# MC50_CPU.net
KiCad netlist of a schematic drawn in Altium Designer
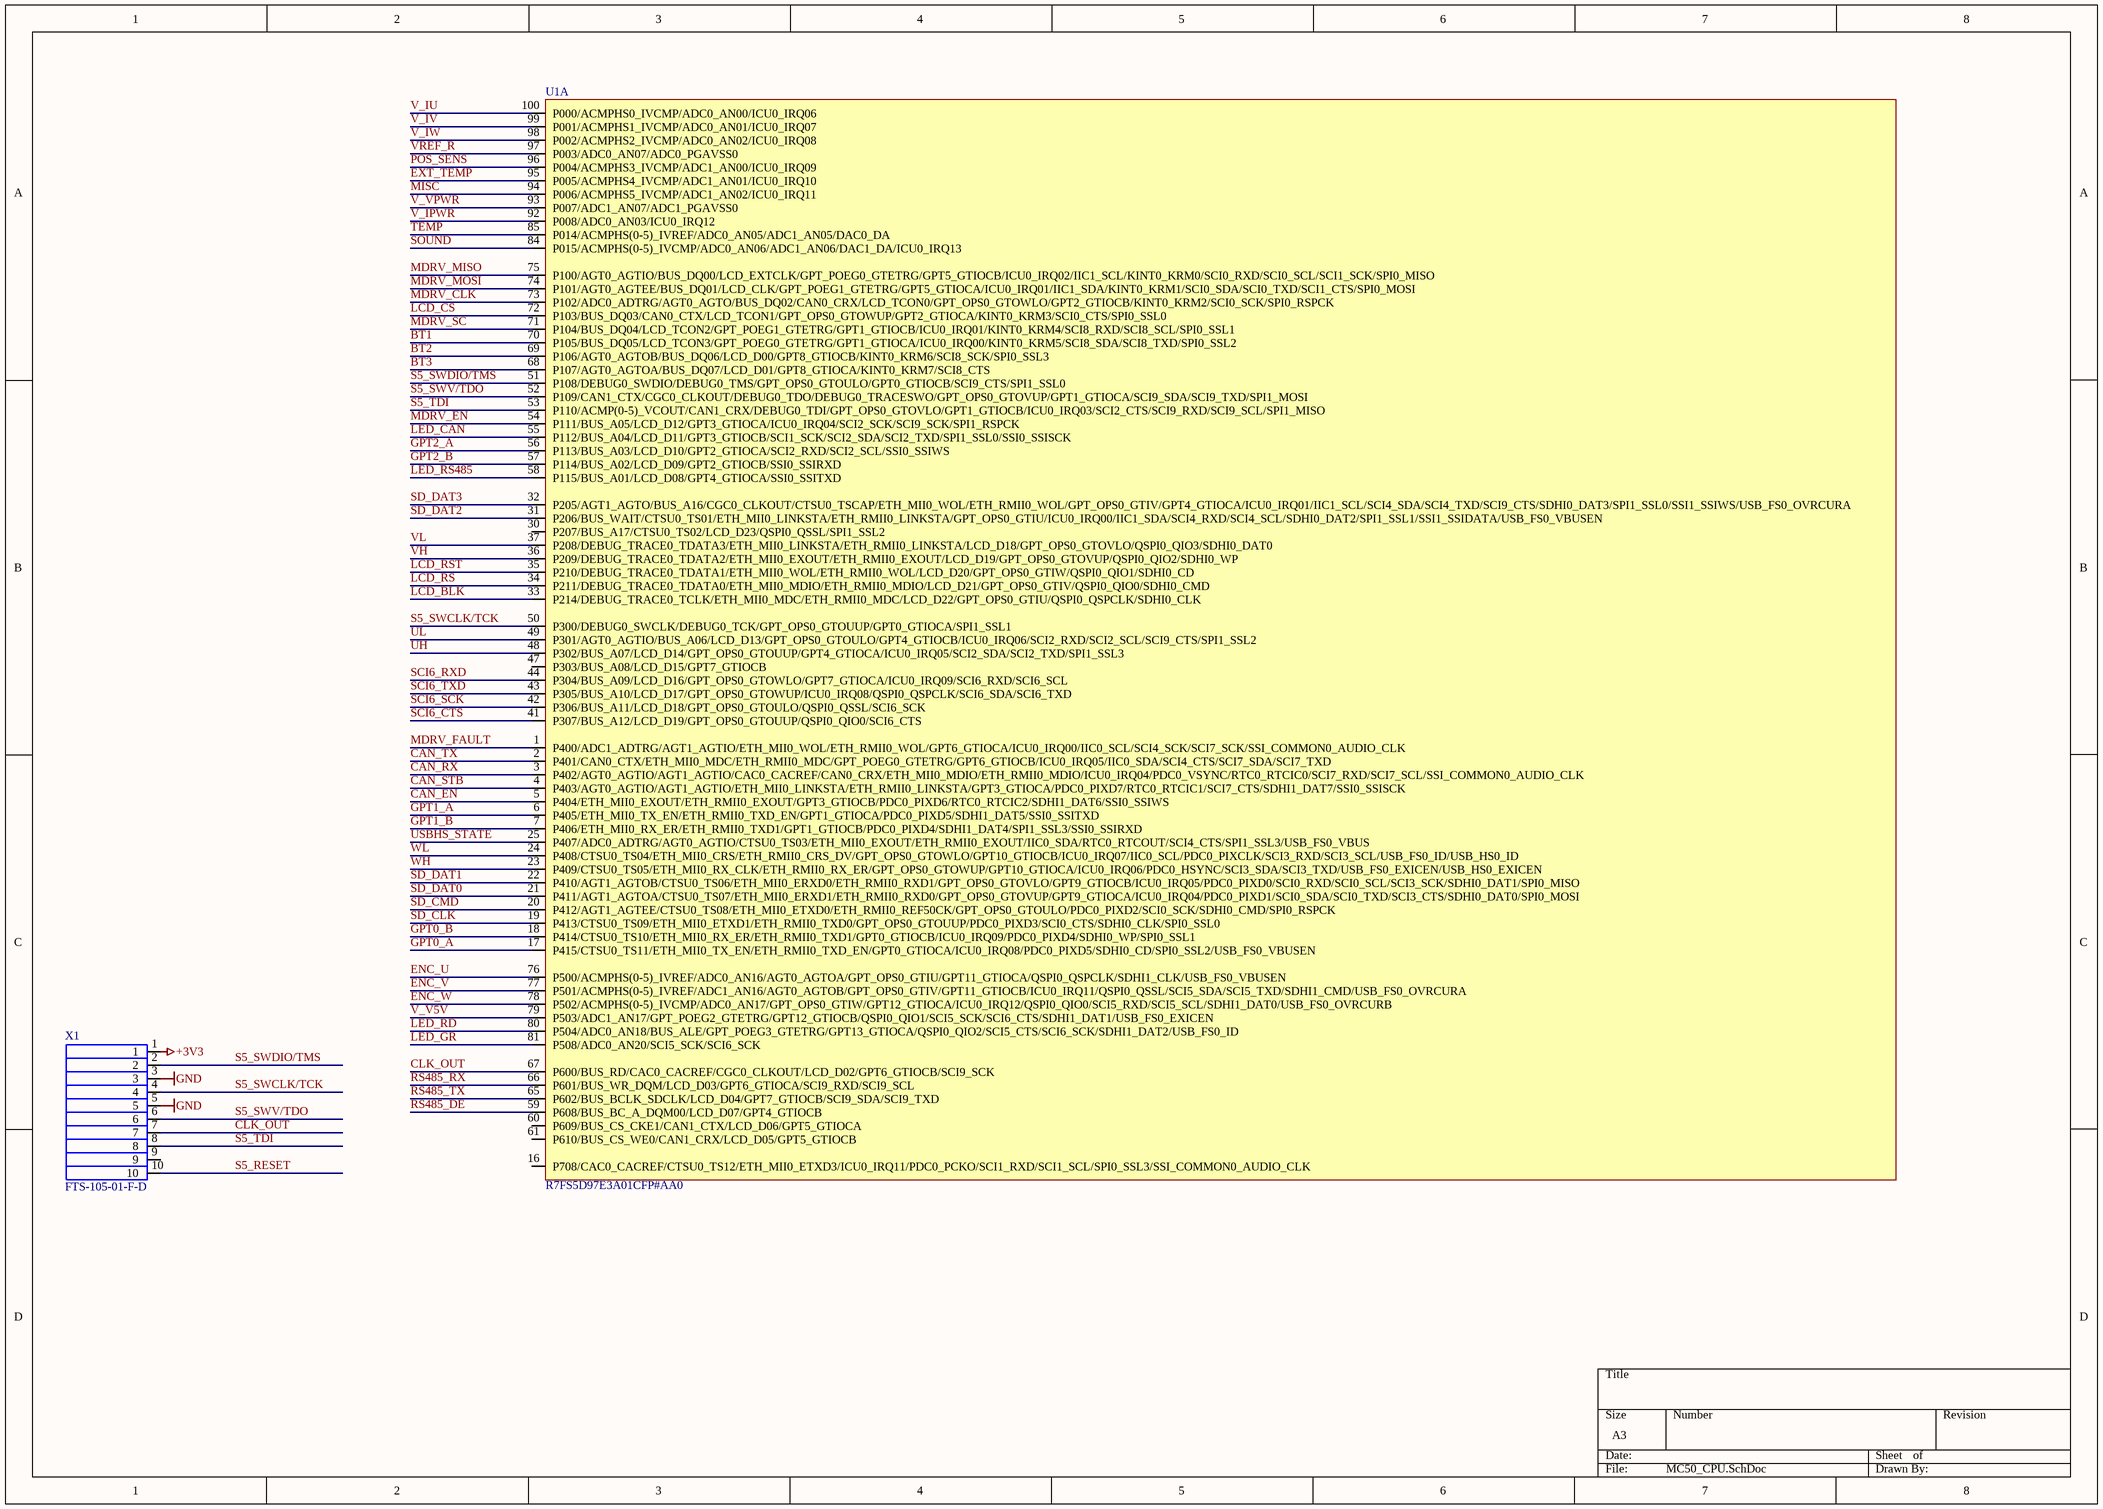
[diagram p0: MC50_CPU.SchDoc]

(export (version "E")
  (design (tool "Eeschema 10.0.6"))
  (components
    (comp (ref "U1")
      (value "R7FS5D97E3A01CFP#AA0")
      (footprint "P-LFQFP100-14x14-0.50")
      (fields (field (name "MANUFACTURER") "Renesas") (field (name "PARTNUM") "968-S5D97E3A01CFPAA0"))
      (libsource (lib "ea_IC_CPU") (part "R7FS5D97E3A01CFP#AA0"))
    )
    (comp (ref "X1")
      (value "FTS-105-01-F-D")
      (footprint "FTS-105-01-F-D")
      (description "Board-To-Board Connector, Vertical, FTS Series, Through Hole, Header, 10, 1.27 mm")
      (fields (field (name "MANUFACTURER") "SAMTEC") (field (name "PARTNUM") "1928242"))
      (libsource (lib "ea_JTAG_SWD") (part "FTS-105-01-F-D"))
    )
  )
  (nets
    (net (code "1") (name "+3V3") (class "Default")
      (node (ref "X1") (pin "1") (pinfunction "1_1") (pintype "passive"))
    )
    (net (code "2") (name "/BT1") (class "Default")
      (node (ref "U1") (pin "70") (pinfunction "P105/BUS_DQ05/LCD_TCON3/GPT_POEG0_GTETRG/GPT1_GTIOCA/ICU0_IRQ00/KINT0_KRM5/SCI8_SDA/SCI8_TXD/SPI0_SSL2_70") (pintype "bidirectional"))
    )
    (net (code "3") (name "/BT2") (class "Default")
      (node (ref "U1") (pin "69") (pinfunction "P106/AGT0_AGTOB/BUS_DQ06/LCD_D00/GPT8_GTIOCB/KINT0_KRM6/SCI8_SCK/SPI0_SSL3_69") (pintype "bidirectional"))
    )
    (net (code "4") (name "/BT3") (class "Default")
      (node (ref "U1") (pin "68") (pinfunction "P107/AGT0_AGTOA/BUS_DQ07/LCD_D01/GPT8_GTIOCA/KINT0_KRM7/SCI8_CTS_68") (pintype "bidirectional"))
    )
    (net (code "5") (name "/CAN_EN") (class "Default")
      (node (ref "U1") (pin "5") (pinfunction "P404/ETH_MII0_EXOUT/ETH_RMII0_EXOUT/GPT3_GTIOCB/PDC0_PIXD6/RTC0_RTCIC2/SDHI1_DAT6/SSI0_SSIWS_5") (pintype "bidirectional"))
    )
    (net (code "6") (name "/CAN_RX") (class "Default")
      (node (ref "U1") (pin "3") (pinfunction "P402/AGT0_AGTIO/AGT1_AGTIO/CAC0_CACREF/CAN0_CRX/ETH_MII0_MDIO/ETH_RMII0_MDIO/ICU0_IRQ04/PDC0_VSYNC/RTC0_RTCIC0/SCI7_RXD/SCI7_SCL/SSI_COMMON0_AUDIO_CLK_3") (pintype "bidirectional"))
    )
    (net (code "7") (name "/CAN_STB") (class "Default")
      (node (ref "U1") (pin "4") (pinfunction "P403/AGT0_AGTIO/AGT1_AGTIO/ETH_MII0_LINKSTA/ETH_RMII0_LINKSTA/GPT3_GTIOCA/PDC0_PIXD7/RTC0_RTCIC1/SCI7_CTS/SDHI1_DAT7/SSI0_SSISCK_4") (pintype "bidirectional"))
    )
    (net (code "8") (name "/CAN_TX") (class "Default")
      (node (ref "U1") (pin "2") (pinfunction "P401/CAN0_CTX/ETH_MII0_MDC/ETH_RMII0_MDC/GPT_POEG0_GTETRG/GPT6_GTIOCB/ICU0_IRQ05/IIC0_SDA/SCI4_CTS/SCI7_SDA/SCI7_TXD_2") (pintype "bidirectional"))
    )
    (net (code "9") (name "/CLK_OUT") (class "Default")
      (node (ref "U1") (pin "67") (pinfunction "P600/BUS_RD/CAC0_CACREF/CGC0_CLKOUT/LCD_D02/GPT6_GTIOCB/SCI9_SCK_67") (pintype "bidirectional"))
      (node (ref "X1") (pin "7") (pinfunction "7_7") (pintype "power_in"))
    )
    (net (code "10") (name "/ENC_U") (class "Default")
      (node (ref "U1") (pin "76") (pinfunction "P500/ACMPHS(0-5)_IVREF/ADC0_AN16/AGT0_AGTOA/GPT_OPS0_GTIU/GPT11_GTIOCA/QSPI0_QSPCLK/SDHI1_CLK/USB_FS0_VBUSEN_76") (pintype "bidirectional"))
    )
    (net (code "11") (name "/ENC_V") (class "Default")
      (node (ref "U1") (pin "77") (pinfunction "P501/ACMPHS(0-5)_IVREF/ADC1_AN16/AGT0_AGTOB/GPT_OPS0_GTIV/GPT11_GTIOCB/ICU0_IRQ11/QSPI0_QSSL/SCI5_SDA/SCI5_TXD/SDHI1_CMD/USB_FS0_OVRCURA_77") (pintype "bidirectional"))
    )
    (net (code "12") (name "/ENC_W") (class "Default")
      (node (ref "U1") (pin "78") (pinfunction "P502/ACMPHS(0-5)_IVCMP/ADC0_AN17/GPT_OPS0_GTIW/GPT12_GTIOCA/ICU0_IRQ12/QSPI0_QIO0/SCI5_RXD/SCI5_SCL/SDHI1_DAT0/USB_FS0_OVRCURB_78") (pintype "bidirectional"))
    )
    (net (code "13") (name "/EXT_TEMP") (class "Default")
      (node (ref "U1") (pin "95") (pinfunction "P005/ACMPHS4_IVCMP/ADC1_AN01/ICU0_IRQ10_95") (pintype "bidirectional"))
    )
    (net (code "14") (name "/GPT0_A") (class "Default")
      (node (ref "U1") (pin "17") (pinfunction "P415/CTSU0_TS11/ETH_MII0_TX_EN/ETH_RMII0_TXD_EN/GPT0_GTIOCA/ICU0_IRQ08/PDC0_PIXD5/SDHI0_CD/SPI0_SSL2/USB_FS0_VBUSEN_17") (pintype "bidirectional"))
    )
    (net (code "15") (name "/GPT0_B") (class "Default")
      (node (ref "U1") (pin "18") (pinfunction "P414/CTSU0_TS10/ETH_MII0_RX_ER/ETH_RMII0_TXD1/GPT0_GTIOCB/ICU0_IRQ09/PDC0_PIXD4/SDHI0_WP/SPI0_SSL1_18") (pintype "bidirectional"))
    )
    (net (code "16") (name "/GPT1_A") (class "Default")
      (node (ref "U1") (pin "6") (pinfunction "P405/ETH_MII0_TX_EN/ETH_RMII0_TXD_EN/GPT1_GTIOCA/PDC0_PIXD5/SDHI1_DAT5/SSI0_SSITXD_6") (pintype "bidirectional"))
    )
    (net (code "17") (name "/GPT1_B") (class "Default")
      (node (ref "U1") (pin "7") (pinfunction "P406/ETH_MII0_RX_ER/ETH_RMII0_TXD1/GPT1_GTIOCB/PDC0_PIXD4/SDHI1_DAT4/SPI1_SSL3/SSI0_SSIRXD_7") (pintype "bidirectional"))
    )
    (net (code "18") (name "/GPT2_A") (class "Default")
      (node (ref "U1") (pin "56") (pinfunction "P113/BUS_A03/LCD_D10/GPT2_GTIOCA/SCI2_RXD/SCI2_SCL/SSI0_SSIWS_56") (pintype "bidirectional"))
    )
    (net (code "19") (name "/GPT2_B") (class "Default")
      (node (ref "U1") (pin "57") (pinfunction "P114/BUS_A02/LCD_D09/GPT2_GTIOCB/SSI0_SSIRXD_57") (pintype "bidirectional"))
    )
    (net (code "20") (name "/LCD_BLK") (class "Default")
      (node (ref "U1") (pin "33") (pinfunction "P214/DEBUG_TRACE0_TCLK/ETH_MII0_MDC/ETH_RMII0_MDC/LCD_D22/GPT_OPS0_GTIU/QSPI0_QSPCLK/SDHI0_CLK_33") (pintype "bidirectional"))
    )
    (net (code "21") (name "/LCD_CS") (class "Default")
      (node (ref "U1") (pin "72") (pinfunction "P103/BUS_DQ03/CAN0_CTX/LCD_TCON1/GPT_OPS0_GTOWUP/GPT2_GTIOCA/KINT0_KRM3/SCI0_CTS/SPI0_SSL0_72") (pintype "bidirectional"))
    )
    (net (code "22") (name "/LCD_RS") (class "Default")
      (node (ref "U1") (pin "34") (pinfunction "P211/DEBUG_TRACE0_TDATA0/ETH_MII0_MDIO/ETH_RMII0_MDIO/LCD_D21/GPT_OPS0_GTIV/QSPI0_QIO0/SDHI0_CMD_34") (pintype "bidirectional"))
    )
    (net (code "23") (name "/LCD_RST") (class "Default")
      (node (ref "U1") (pin "35") (pinfunction "P210/DEBUG_TRACE0_TDATA1/ETH_MII0_WOL/ETH_RMII0_WOL/LCD_D20/GPT_OPS0_GTIW/QSPI0_QIO1/SDHI0_CD_35") (pintype "bidirectional"))
    )
    (net (code "24") (name "/LED_CAN") (class "Default")
      (node (ref "U1") (pin "55") (pinfunction "P112/BUS_A04/LCD_D11/GPT3_GTIOCB/SCI1_SCK/SCI2_SDA/SCI2_TXD/SPI1_SSL0/SSI0_SSISCK_55") (pintype "bidirectional"))
    )
    (net (code "25") (name "/LED_GR") (class "Default")
      (node (ref "U1") (pin "81") (pinfunction "P508/ADC0_AN20/SCI5_SCK/SCI6_SCK_81") (pintype "bidirectional"))
    )
    (net (code "26") (name "/LED_RD") (class "Default")
      (node (ref "U1") (pin "80") (pinfunction "P504/ADC0_AN18/BUS_ALE/GPT_POEG3_GTETRG/GPT13_GTIOCA/QSPI0_QIO2/SCI5_CTS/SCI6_SCK/SDHI1_DAT2/USB_FS0_ID_80") (pintype "bidirectional"))
    )
    (net (code "27") (name "/LED_RS485") (class "Default")
      (node (ref "U1") (pin "58") (pinfunction "P115/BUS_A01/LCD_D08/GPT4_GTIOCA/SSI0_SSITXD_58") (pintype "bidirectional"))
    )
    (net (code "28") (name "/MDRV_CLK") (class "Default")
      (node (ref "U1") (pin "73") (pinfunction "P102/ADC0_ADTRG/AGT0_AGTO/BUS_DQ02/CAN0_CRX/LCD_TCON0/GPT_OPS0_GTOWLO/GPT2_GTIOCB/KINT0_KRM2/SCI0_SCK/SPI0_RSPCK_73") (pintype "bidirectional"))
    )
    (net (code "29") (name "/MDRV_EN") (class "Default")
      (node (ref "U1") (pin "54") (pinfunction "P111/BUS_A05/LCD_D12/GPT3_GTIOCA/ICU0_IRQ04/SCI2_SCK/SCI9_SCK/SPI1_RSPCK_54") (pintype "bidirectional"))
    )
    (net (code "30") (name "/MDRV_FAULT") (class "Default")
      (node (ref "U1") (pin "1") (pinfunction "P400/ADC1_ADTRG/AGT1_AGTIO/ETH_MII0_WOL/ETH_RMII0_WOL/GPT6_GTIOCA/ICU0_IRQ00/IIC0_SCL/SCI4_SCK/SCI7_SCK/SSI_COMMON0_AUDIO_CLK_1") (pintype "bidirectional"))
    )
    (net (code "31") (name "/MDRV_MISO") (class "Default")
      (node (ref "U1") (pin "75") (pinfunction "P100/AGT0_AGTIO/BUS_DQ00/LCD_EXTCLK/GPT_POEG0_GTETRG/GPT5_GTIOCB/ICU0_IRQ02/IIC1_SCL/KINT0_KRM0/SCI0_RXD/SCI0_SCL/SCI1_SCK/SPI0_MISO_75") (pintype "bidirectional"))
    )
    (net (code "32") (name "/MDRV_MOSI") (class "Default")
      (node (ref "U1") (pin "74") (pinfunction "P101/AGT0_AGTEE/BUS_DQ01/LCD_CLK/GPT_POEG1_GTETRG/GPT5_GTIOCA/ICU0_IRQ01/IIC1_SDA/KINT0_KRM1/SCI0_SDA/SCI0_TXD/SCI1_CTS/SPI0_MOSI_74") (pintype "bidirectional"))
    )
    (net (code "33") (name "/MDRV_SC") (class "Default")
      (node (ref "U1") (pin "71") (pinfunction "P104/BUS_DQ04/LCD_TCON2/GPT_POEG1_GTETRG/GPT1_GTIOCB/ICU0_IRQ01/KINT0_KRM4/SCI8_RXD/SCI8_SCL/SPI0_SSL1_71") (pintype "bidirectional"))
    )
    (net (code "34") (name "/MISC") (class "Default")
      (node (ref "U1") (pin "94") (pinfunction "P006/ACMPHS5_IVCMP/ADC1_AN02/ICU0_IRQ11_94") (pintype "bidirectional"))
    )
    (net (code "35") (name "/POS_SENS") (class "Default")
      (node (ref "U1") (pin "96") (pinfunction "P004/ACMPHS3_IVCMP/ADC1_AN00/ICU0_IRQ09_96") (pintype "bidirectional"))
    )
    (net (code "36") (name "/RS485_DE") (class "Default")
      (node (ref "U1") (pin "59") (pinfunction "P608/BUS_BC_A_DQM00/LCD_D07/GPT4_GTIOCB_59") (pintype "bidirectional"))
    )
    (net (code "37") (name "/RS485_RX") (class "Default")
      (node (ref "U1") (pin "66") (pinfunction "P601/BUS_WR_DQM/LCD_D03/GPT6_GTIOCA/SCI9_RXD/SCI9_SCL_66") (pintype "bidirectional"))
    )
    (net (code "38") (name "/RS485_TX") (class "Default")
      (node (ref "U1") (pin "65") (pinfunction "P602/BUS_BCLK_SDCLK/LCD_D04/GPT7_GTIOCB/SCI9_SDA/SCI9_TXD_65") (pintype "bidirectional"))
    )
    (net (code "39") (name "/S5_RESET") (class "Default")
      (node (ref "X1") (pin "10") (pinfunction "10_10") (pintype "power_in"))
    )
    (net (code "40") (name "/S5_SWCLK{slash}TCK") (class "Default")
      (node (ref "U1") (pin "50") (pinfunction "P300/DEBUG0_SWCLK/DEBUG0_TCK/GPT_OPS0_GTOUUP/GPT0_GTIOCA/SPI1_SSL1_50") (pintype "bidirectional"))
      (node (ref "X1") (pin "4") (pinfunction "4_4") (pintype "passive"))
    )
    (net (code "41") (name "/S5_SWDIO{slash}TMS") (class "Default")
      (node (ref "U1") (pin "51") (pinfunction "P108/DEBUG0_SWDIO/DEBUG0_TMS/GPT_OPS0_GTOULO/GPT0_GTIOCB/SCI9_CTS/SPI1_SSL0_51") (pintype "bidirectional"))
      (node (ref "X1") (pin "2") (pinfunction "2_2") (pintype "passive"))
    )
    (net (code "42") (name "/S5_SWV{slash}TDO") (class "Default")
      (node (ref "U1") (pin "52") (pinfunction "P109/CAN1_CTX/CGC0_CLKOUT/DEBUG0_TDO/DEBUG0_TRACESWO/GPT_OPS0_GTOVUP/GPT1_GTIOCA/SCI9_SDA/SCI9_TXD/SPI1_MOSI_52") (pintype "bidirectional"))
      (node (ref "X1") (pin "6") (pinfunction "6_6") (pintype "power_in"))
    )
    (net (code "43") (name "/S5_TDI") (class "Default")
      (node (ref "U1") (pin "53") (pinfunction "P110/ACMP(0-5)_VCOUT/CAN1_CRX/DEBUG0_TDI/GPT_OPS0_GTOVLO/GPT1_GTIOCB/ICU0_IRQ03/SCI2_CTS/SCI9_RXD/SCI9_SCL/SPI1_MISO_53") (pintype "bidirectional"))
      (node (ref "X1") (pin "8") (pinfunction "8_8") (pintype "power_in"))
    )
    (net (code "44") (name "/SCI6_CTS") (class "Default")
      (node (ref "U1") (pin "41") (pinfunction "P307/BUS_A12/LCD_D19/GPT_OPS0_GTOUUP/QSPI0_QIO0/SCI6_CTS_41") (pintype "bidirectional"))
    )
    (net (code "45") (name "/SCI6_RXD") (class "Default")
      (node (ref "U1") (pin "44") (pinfunction "P304/BUS_A09/LCD_D16/GPT_OPS0_GTOWLO/GPT7_GTIOCA/ICU0_IRQ09/SCI6_RXD/SCI6_SCL_44") (pintype "bidirectional"))
    )
    (net (code "46") (name "/SCI6_SCK") (class "Default")
      (node (ref "U1") (pin "42") (pinfunction "P306/BUS_A11/LCD_D18/GPT_OPS0_GTOULO/QSPI0_QSSL/SCI6_SCK_42") (pintype "bidirectional"))
    )
    (net (code "47") (name "/SCI6_TXD") (class "Default")
      (node (ref "U1") (pin "43") (pinfunction "P305/BUS_A10/LCD_D17/GPT_OPS0_GTOWUP/ICU0_IRQ08/QSPI0_QSPCLK/SCI6_SDA/SCI6_TXD_43") (pintype "bidirectional"))
    )
    (net (code "48") (name "/SD_CLK") (class "Default")
      (node (ref "U1") (pin "19") (pinfunction "P413/CTSU0_TS09/ETH_MII0_ETXD1/ETH_RMII0_TXD0/GPT_OPS0_GTOUUP/PDC0_PIXD3/SCI0_CTS/SDHI0_CLK/SPI0_SSL0_19") (pintype "bidirectional"))
    )
    (net (code "49") (name "/SD_CMD") (class "Default")
      (node (ref "U1") (pin "20") (pinfunction "P412/AGT1_AGTEE/CTSU0_TS08/ETH_MII0_ETXD0/ETH_RMII0_REF50CK/GPT_OPS0_GTOULO/PDC0_PIXD2/SCI0_SCK/SDHI0_CMD/SPI0_RSPCK_20") (pintype "bidirectional"))
    )
    (net (code "50") (name "/SD_DAT0") (class "Default")
      (node (ref "U1") (pin "21") (pinfunction "P411/AGT1_AGTOA/CTSU0_TS07/ETH_MII0_ERXD1/ETH_RMII0_RXD0/GPT_OPS0_GTOVUP/GPT9_GTIOCA/ICU0_IRQ04/PDC0_PIXD1/SCI0_SDA/SCI0_TXD/SCI3_CTS/SDHI0_DAT0/SPI0_MOSI_21") (pintype "bidirectional"))
    )
    (net (code "51") (name "/SD_DAT1") (class "Default")
      (node (ref "U1") (pin "22") (pinfunction "P410/AGT1_AGTOB/CTSU0_TS06/ETH_MII0_ERXD0/ETH_RMII0_RXD1/GPT_OPS0_GTOVLO/GPT9_GTIOCB/ICU0_IRQ05/PDC0_PIXD0/SCI0_RXD/SCI0_SCL/SCI3_SCK/SDHI0_DAT1/SPI0_MISO_22") (pintype "bidirectional"))
    )
    (net (code "52") (name "/SD_DAT2") (class "Default")
      (node (ref "U1") (pin "31") (pinfunction "P206/BUS_WAIT/CTSU0_TS01/ETH_MII0_LINKSTA/ETH_RMII0_LINKSTA/GPT_OPS0_GTIU/ICU0_IRQ00/IIC1_SDA/SCI4_RXD/SCI4_SCL/SDHI0_DAT2/SPI1_SSL1/SSI1_SSIDATA/USB_FS0_VBUSEN_31") (pintype "bidirectional"))
    )
    (net (code "53") (name "/SD_DAT3") (class "Default")
      (node (ref "U1") (pin "32") (pinfunction "P205/AGT1_AGTO/BUS_A16/CGC0_CLKOUT/CTSU0_TSCAP/ETH_MII0_WOL/ETH_RMII0_WOL/GPT_OPS0_GTIV/GPT4_GTIOCA/ICU0_IRQ01/IIC1_SCL/SCI4_SDA/SCI4_TXD/SCI9_CTS/SDHI0_DAT3/SPI1_SSL0/SSI1_SSIWS/USB_FS0_OVRCURA_32") (pintype "bidirectional"))
    )
    (net (code "54") (name "/SOUND") (class "Default")
      (node (ref "U1") (pin "84") (pinfunction "P015/ACMPHS(0-5)_IVCMP/ADC0_AN06/ADC1_AN06/DAC1_DA/ICU0_IRQ13_84") (pintype "bidirectional"))
    )
    (net (code "55") (name "/TEMP") (class "Default")
      (node (ref "U1") (pin "85") (pinfunction "P014/ACMPHS(0-5)_IVREF/ADC0_AN05/ADC1_AN05/DAC0_DA_85") (pintype "bidirectional"))
    )
    (net (code "56") (name "/UH") (class "Default")
      (node (ref "U1") (pin "48") (pinfunction "P302/BUS_A07/LCD_D14/GPT_OPS0_GTOUUP/GPT4_GTIOCA/ICU0_IRQ05/SCI2_SDA/SCI2_TXD/SPI1_SSL3_48") (pintype "bidirectional"))
    )
    (net (code "57") (name "/UL") (class "Default")
      (node (ref "U1") (pin "49") (pinfunction "P301/AGT0_AGTIO/BUS_A06/LCD_D13/GPT_OPS0_GTOULO/GPT4_GTIOCB/ICU0_IRQ06/SCI2_RXD/SCI2_SCL/SCI9_CTS/SPI1_SSL2_49") (pintype "bidirectional"))
    )
    (net (code "58") (name "/USBHS_STATE") (class "Default")
      (node (ref "U1") (pin "25") (pinfunction "P407/ADC0_ADTRG/AGT0_AGTIO/CTSU0_TS03/ETH_MII0_EXOUT/ETH_RMII0_EXOUT/IIC0_SDA/RTC0_RTCOUT/SCI4_CTS/SPI1_SSL3/USB_FS0_VBUS_25") (pintype "bidirectional"))
    )
    (net (code "59") (name "/VH") (class "Default")
      (node (ref "U1") (pin "36") (pinfunction "P209/DEBUG_TRACE0_TDATA2/ETH_MII0_EXOUT/ETH_RMII0_EXOUT/LCD_D19/GPT_OPS0_GTOVUP/QSPI0_QIO2/SDHI0_WP_36") (pintype "bidirectional"))
    )
    (net (code "60") (name "/VL") (class "Default")
      (node (ref "U1") (pin "37") (pinfunction "P208/DEBUG_TRACE0_TDATA3/ETH_MII0_LINKSTA/ETH_RMII0_LINKSTA/LCD_D18/GPT_OPS0_GTOVLO/QSPI0_QIO3/SDHI0_DAT0_37") (pintype "bidirectional"))
    )
    (net (code "61") (name "/VREF_R") (class "Default")
      (node (ref "U1") (pin "97") (pinfunction "P003/ADC0_AN07/ADC0_PGAVSS0_97") (pintype "bidirectional"))
    )
    (net (code "62") (name "/V_IPWR") (class "Default")
      (node (ref "U1") (pin "92") (pinfunction "P008/ADC0_AN03/ICU0_IRQ12_92") (pintype "bidirectional"))
    )
    (net (code "63") (name "/V_IU") (class "Default")
      (node (ref "U1") (pin "100") (pinfunction "P000/ACMPHS0_IVCMP/ADC0_AN00/ICU0_IRQ06_100") (pintype "bidirectional"))
    )
    (net (code "64") (name "/V_IV") (class "Default")
      (node (ref "U1") (pin "99") (pinfunction "P001/ACMPHS1_IVCMP/ADC0_AN01/ICU0_IRQ07_99") (pintype "bidirectional"))
    )
    (net (code "65") (name "/V_IW") (class "Default")
      (node (ref "U1") (pin "98") (pinfunction "P002/ACMPHS2_IVCMP/ADC0_AN02/ICU0_IRQ08_98") (pintype "bidirectional"))
    )
    (net (code "66") (name "/V_V5V") (class "Default")
      (node (ref "U1") (pin "79") (pinfunction "P503/ADC1_AN17/GPT_POEG2_GTETRG/GPT12_GTIOCB/QSPI0_QIO1/SCI5_SCK/SCI6_CTS/SDHI1_DAT1/USB_FS0_EXICEN_79") (pintype "bidirectional"))
    )
    (net (code "67") (name "/V_VPWR") (class "Default")
      (node (ref "U1") (pin "93") (pinfunction "P007/ADC1_AN07/ADC1_PGAVSS0_93") (pintype "bidirectional"))
    )
    (net (code "68") (name "/WH") (class "Default")
      (node (ref "U1") (pin "23") (pinfunction "P409/CTSU0_TS05/ETH_MII0_RX_CLK/ETH_RMII0_RX_ER/GPT_OPS0_GTOWUP/GPT10_GTIOCA/ICU0_IRQ06/PDC0_HSYNC/SCI3_SDA/SCI3_TXD/USB_FS0_EXICEN/USB_HS0_EXICEN_23") (pintype "bidirectional"))
    )
    (net (code "69") (name "/WL") (class "Default")
      (node (ref "U1") (pin "24") (pinfunction "P408/CTSU0_TS04/ETH_MII0_CRS/ETH_RMII0_CRS_DV/GPT_OPS0_GTOWLO/GPT10_GTIOCB/ICU0_IRQ07/IIC0_SCL/PDC0_PIXCLK/SCI3_RXD/SCI3_SCL/USB_FS0_ID/USB_HS0_ID_24") (pintype "bidirectional"))
    )
    (net (code "70") (name "GND") (class "Default")
      (node (ref "X1") (pin "3") (pinfunction "3_3") (pintype "passive"))
      (node (ref "X1") (pin "5") (pinfunction "5_5") (pintype "power_in"))
    )
    (net (code "71") (name "unconnected-(U1A-P207{slash}BUS_A17{slash}CTSU0_TS02{slash}LCD_D23{slash}QSPI0_QSSL{slash}SPI1_SSL2-Pad30)") (class "Default")
      (node (ref "U1") (pin "30") (pinfunction "P207/BUS_A17/CTSU0_TS02/LCD_D23/QSPI0_QSSL/SPI1_SSL2_30") (pintype "bidirectional"))
    )
    (net (code "72") (name "unconnected-(U1A-P303{slash}BUS_A08{slash}LCD_D15{slash}GPT7_GTIOCB-Pad47)") (class "Default")
      (node (ref "U1") (pin "47") (pinfunction "P303/BUS_A08/LCD_D15/GPT7_GTIOCB_47") (pintype "bidirectional"))
    )
    (net (code "73") (name "unconnected-(U1A-P609{slash}BUS_CS_CKE1{slash}CAN1_CTX{slash}LCD_D06{slash}GPT5_GTIOCA-Pad60)") (class "Default")
      (node (ref "U1") (pin "60") (pinfunction "P609/BUS_CS_CKE1/CAN1_CTX/LCD_D06/GPT5_GTIOCA_60") (pintype "bidirectional"))
    )
    (net (code "74") (name "unconnected-(U1A-P610{slash}BUS_CS_WE0{slash}CAN1_CRX{slash}LCD_D05{slash}GPT5_GTIOCB-Pad61)") (class "Default")
      (node (ref "U1") (pin "61") (pinfunction "P610/BUS_CS_WE0/CAN1_CRX/LCD_D05/GPT5_GTIOCB_61") (pintype "bidirectional"))
    )
    (net (code "75") (name "unconnected-(U1A-P708{slash}CAC0_CACREF{slash}CTSU0_TS12{slash}ETH_MII0_ETXD3{slash}ICU0_IRQ11{slash}PDC0_PCKO{slash}SCI1_RXD{slash}SCI1_SCL{slash}SPI0_SSL3{slash}SSI_COMMON0_AUDIO_CLK-Pad16)") (class "Default")
      (node (ref "U1") (pin "16") (pinfunction "P708/CAC0_CACREF/CTSU0_TS12/ETH_MII0_ETXD3/ICU0_IRQ11/PDC0_PCKO/SCI1_RXD/SCI1_SCL/SPI0_SSL3/SSI_COMMON0_AUDIO_CLK_16") (pintype "bidirectional"))
    )
    (net (code "76") (name "unconnected-(X1-Pad9)") (class "Default")
      (node (ref "X1") (pin "9") (pinfunction "9_9") (pintype "power_in"))
    )
  )
)
